# MicroBreeze.net
KiCad netlist of a schematic drawn in EAGLE
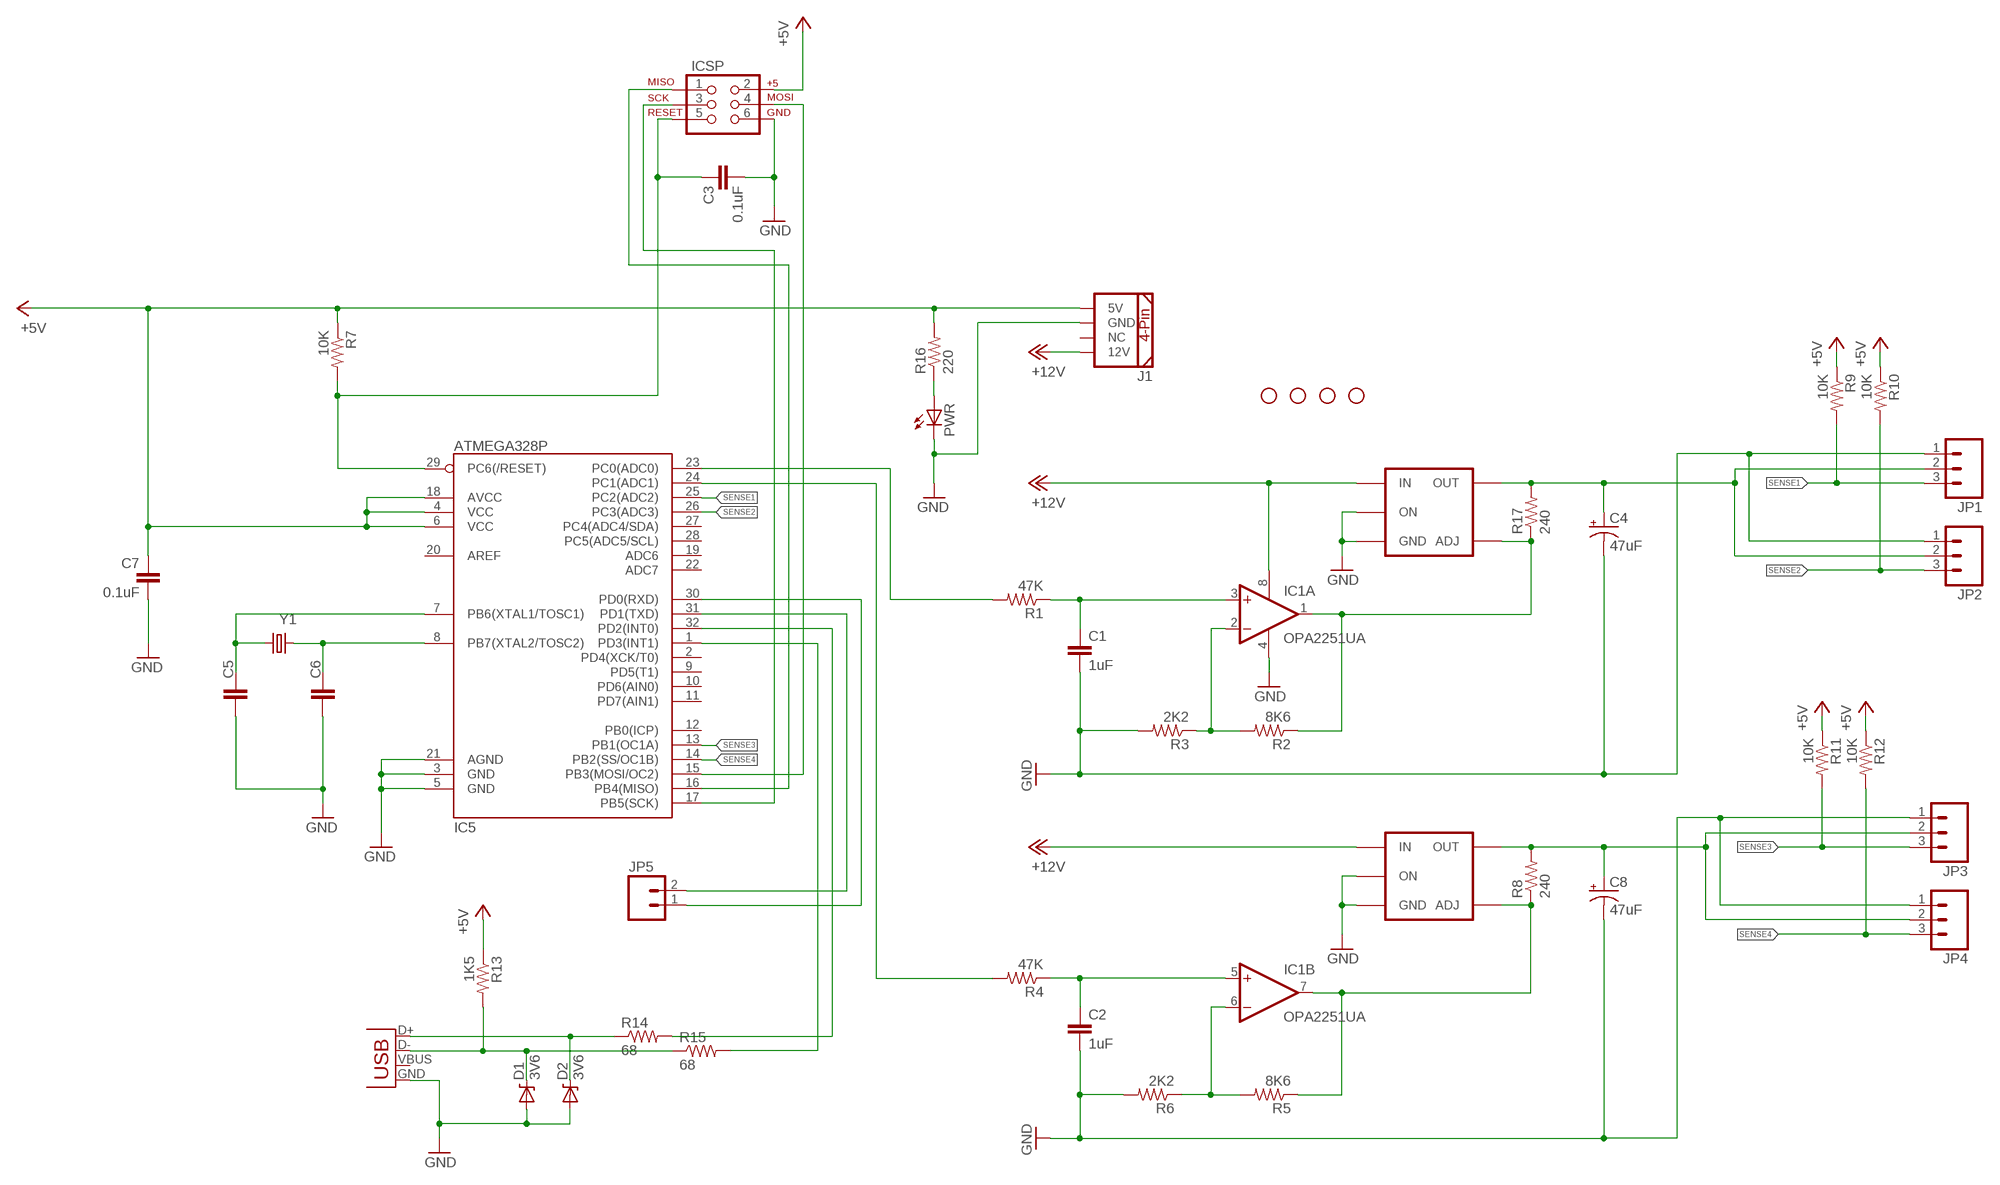
[diagram p0: schematic, sheet 1]

(export (version "E")
  (design (tool "Eeschema 10.0.6"))
  (components
    (comp (ref "C1")
      (value "1uF")
      (footprint "eagle-import:0805")
      (libsource (lib "eagle-import") (part "CAP0805"))
    )
    (comp (ref "C2")
      (value "1uF")
      (footprint "eagle-import:0805")
      (libsource (lib "eagle-import") (part "CAP0805"))
    )
    (comp (ref "C3")
      (value "0.1uF")
      (footprint "eagle-import:0805")
      (libsource (lib "eagle-import") (part "CAP0805"))
    )
    (comp (ref "C4")
      (value "47uF")
      (footprint "eagle-import:EIA3528")
      (libsource (lib "eagle-import") (part "47UF-TANT"))
    )
    (comp (ref "C5")
      (value ".22uF")
      (footprint "eagle-import:0805")
      (libsource (lib "eagle-import") (part "CAP0805"))
    )
    (comp (ref "C6")
      (value ".22uF")
      (footprint "eagle-import:0805")
      (libsource (lib "eagle-import") (part "CAP0805"))
    )
    (comp (ref "C7")
      (value "0.1uF")
      (footprint "eagle-import:0805")
      (libsource (lib "eagle-import") (part "CAP0805"))
    )
    (comp (ref "C8")
      (value "47uF")
      (footprint "eagle-import:EIA3528")
      (libsource (lib "eagle-import") (part "47UF-TANT"))
    )
    (comp (ref "D1")
      (value "3V6")
      (footprint "eagle-import:SOD-323")
      (libsource (lib "eagle-import") (part "DIODE-ZENER-BZT52"))
    )
    (comp (ref "D2")
      (value "3V6")
      (footprint "eagle-import:SOD-323")
      (libsource (lib "eagle-import") (part "DIODE-ZENER-BZT52"))
    )
    (comp (ref "HOLE1")
      (value "STAND-OFF")
      (footprint "eagle-import:STAND-OFF")
      (libsource (lib "eagle-import") (part "STAND-OFF"))
    )
    (comp (ref "HOLE2")
      (value "STAND-OFF")
      (footprint "eagle-import:STAND-OFF")
      (libsource (lib "eagle-import") (part "STAND-OFF"))
    )
    (comp (ref "HOLE3")
      (value "STAND-OFF")
      (footprint "eagle-import:STAND-OFF")
      (libsource (lib "eagle-import") (part "STAND-OFF"))
    )
    (comp (ref "HOLE4")
      (value "STAND-OFF")
      (footprint "eagle-import:STAND-OFF")
      (libsource (lib "eagle-import") (part "STAND-OFF"))
    )
    (comp (ref "IC1")
      (value "OPA2251UA")
      (footprint "eagle-import:SO08")
      (libsource (lib "eagle-import") (part "OPA2UA251"))
    )
    (comp (ref "IC3")
      (value "LM2941TO220-V")
      (footprint "eagle-import:TO220-51")
      (libsource (lib "eagle-import") (part "LM2941TO220-V"))
    )
    (comp (ref "IC4")
      (value "LM2941TO220-V")
      (footprint "eagle-import:TO220-51")
      (libsource (lib "eagle-import") (part "LM2941TO220-V"))
    )
    (comp (ref "IC5")
      (value "ATMEGA328P")
      (footprint "eagle-import:TQFP32-08")
      (libsource (lib "eagle-import") (part "ATMEGA328_SMT"))
    )
    (comp (ref "ICSP")
      (value "AVR_SPI_PRG_6PTH")
      (footprint "eagle-import:2X3")
      (libsource (lib "eagle-import") (part "AVR_SPI_PRG_6PTH"))
    )
    (comp (ref "J1")
      (value "COMPUTER-PERIPHERAL-POWERVERTICAL")
      (footprint "eagle-import:COMPUTER-PERIPHERAL-POWER")
      (libsource (lib "eagle-import") (part "COMPUTER-PERIPHERAL-POWERVERTICAL"))
    )
    (comp (ref "JP1")
      (value "M03POLAR")
      (footprint "eagle-import:MOLEX-1X3")
      (libsource (lib "eagle-import") (part "M03POLAR"))
    )
    (comp (ref "JP2")
      (value "M03POLAR")
      (footprint "eagle-import:MOLEX-1X3")
      (libsource (lib "eagle-import") (part "M03POLAR"))
    )
    (comp (ref "JP3")
      (value "M03POLAR")
      (footprint "eagle-import:MOLEX-1X3")
      (libsource (lib "eagle-import") (part "M03POLAR"))
    )
    (comp (ref "JP4")
      (value "M03POLAR")
      (footprint "eagle-import:MOLEX-1X3")
      (libsource (lib "eagle-import") (part "M03POLAR"))
    )
    (comp (ref "JP5")
      (value "M02PTH")
      (footprint "eagle-import:1X02")
      (libsource (lib "eagle-import") (part "M02PTH"))
    )
    (comp (ref "PWR")
      (value "LED1206")
      (footprint "eagle-import:LED-1206")
      (libsource (lib "eagle-import") (part "LED1206"))
    )
    (comp (ref "R1")
      (value "47K")
      (footprint "eagle-import:0805")
      (libsource (lib "eagle-import") (part "RESISTOR0805-RES"))
    )
    (comp (ref "R2")
      (value "8K6")
      (footprint "eagle-import:0805")
      (libsource (lib "eagle-import") (part "RESISTOR0805-RES"))
    )
    (comp (ref "R3")
      (value "2K2")
      (footprint "eagle-import:0805")
      (libsource (lib "eagle-import") (part "RESISTOR0805-RES"))
    )
    (comp (ref "R4")
      (value "47K")
      (footprint "eagle-import:0805")
      (libsource (lib "eagle-import") (part "RESISTOR0805-RES"))
    )
    (comp (ref "R5")
      (value "8K6")
      (footprint "eagle-import:0805")
      (libsource (lib "eagle-import") (part "RESISTOR0805-RES"))
    )
    (comp (ref "R6")
      (value "2K2")
      (footprint "eagle-import:0805")
      (libsource (lib "eagle-import") (part "RESISTOR0805-RES"))
    )
    (comp (ref "R7")
      (value "10K")
      (footprint "eagle-import:0805")
      (libsource (lib "eagle-import") (part "RESISTOR0805-RES"))
    )
    (comp (ref "R8")
      (value "240")
      (footprint "eagle-import:0805")
      (libsource (lib "eagle-import") (part "RESISTOR0805-RES"))
    )
    (comp (ref "R9")
      (value "10K")
      (footprint "eagle-import:0805")
      (libsource (lib "eagle-import") (part "RESISTOR0805-RES"))
    )
    (comp (ref "R10")
      (value "10K")
      (footprint "eagle-import:0805")
      (libsource (lib "eagle-import") (part "RESISTOR0805-RES"))
    )
    (comp (ref "R11")
      (value "10K")
      (footprint "eagle-import:0805")
      (libsource (lib "eagle-import") (part "RESISTOR0805-RES"))
    )
    (comp (ref "R12")
      (value "10K")
      (footprint "eagle-import:0805")
      (libsource (lib "eagle-import") (part "RESISTOR0805-RES"))
    )
    (comp (ref "R13")
      (value "1K5")
      (footprint "eagle-import:0805")
      (libsource (lib "eagle-import") (part "RESISTOR0805-RES"))
    )
    (comp (ref "R14")
      (value "68")
      (footprint "eagle-import:0805")
      (libsource (lib "eagle-import") (part "RESISTOR0805-RES"))
    )
    (comp (ref "R15")
      (value "68")
      (footprint "eagle-import:0805")
      (libsource (lib "eagle-import") (part "RESISTOR0805-RES"))
    )
    (comp (ref "R16")
      (value "220")
      (footprint "eagle-import:0805")
      (libsource (lib "eagle-import") (part "RESISTOR0805-RES"))
    )
    (comp (ref "R17")
      (value "240")
      (footprint "eagle-import:0805")
      (libsource (lib "eagle-import") (part "RESISTOR0805-RES"))
    )
    (comp (ref "USB")
      (value "USB-A-SMD")
      (footprint "eagle-import:USB-A-S-NOSILK-FEMALE")
      (libsource (lib "eagle-import") (part "USB-A-SMD"))
    )
    (comp (ref "Y1")
      (value "16MHZ")
      (footprint "eagle-import:HC49US")
      (libsource (lib "eagle-import") (part "CRYSTALHC49US"))
    )
  )
  (nets
    (net (code "1") (name "+5V") (class "Default")
      (node (ref "C7") (pin "1") (pinfunction "1_1") (pintype "passive"))
      (node (ref "IC5") (pin "18") (pinfunction "AVCC_18") (pintype "bidirectional"))
      (node (ref "IC5") (pin "4") (pinfunction "VCC_4") (pintype "bidirectional"))
      (node (ref "IC5") (pin "6") (pinfunction "VCC_6") (pintype "bidirectional"))
      (node (ref "ICSP") (pin "2") (pinfunction "2_2") (pintype "passive"))
      (node (ref "J1") (pin "5V") (pinfunction "5V_5V") (pintype "passive"))
      (node (ref "R10") (pin "1") (pinfunction "1_1") (pintype "passive"))
      (node (ref "R11") (pin "1") (pinfunction "1_1") (pintype "passive"))
      (node (ref "R12") (pin "1") (pinfunction "1_1") (pintype "passive"))
      (node (ref "R13") (pin "1") (pinfunction "1_1") (pintype "passive"))
      (node (ref "R16") (pin "2") (pinfunction "2_2") (pintype "passive"))
      (node (ref "R7") (pin "1") (pinfunction "1_1") (pintype "passive"))
      (node (ref "R9") (pin "1") (pinfunction "1_1") (pintype "passive"))
    )
    (net (code "2") (name "+12V") (class "Default")
      (node (ref "IC1") (pin "8") (pinfunction "V+_8") (pintype "power_in"))
      (node (ref "IC3") (pin "4") (pinfunction "IN_4") (pintype "bidirectional"))
      (node (ref "IC4") (pin "4") (pinfunction "IN_4") (pintype "bidirectional"))
      (node (ref "J1") (pin "12V") (pinfunction "12V_12V") (pintype "passive"))
    )
    (net (code "3") (name "GND") (class "Default")
      (node (ref "C1") (pin "2") (pinfunction "2_2") (pintype "passive"))
      (node (ref "C2") (pin "2") (pinfunction "2_2") (pintype "passive"))
      (node (ref "C3") (pin "2") (pinfunction "2_2") (pintype "passive"))
      (node (ref "C4") (pin "C") (pinfunction "-_C") (pintype "passive"))
      (node (ref "C5") (pin "2") (pinfunction "2_2") (pintype "passive"))
      (node (ref "C6") (pin "2") (pinfunction "2_2") (pintype "passive"))
      (node (ref "C7") (pin "2") (pinfunction "2_2") (pintype "passive"))
      (node (ref "C8") (pin "C") (pinfunction "-_C") (pintype "passive"))
      (node (ref "D1") (pin "2") (pinfunction "A_2") (pintype "passive"))
      (node (ref "D2") (pin "2") (pinfunction "A_2") (pintype "passive"))
      (node (ref "IC1") (pin "4") (pinfunction "V-_4") (pintype "power_in"))
      (node (ref "IC3") (pin "2") (pinfunction "ON_2") (pintype "bidirectional"))
      (node (ref "IC3") (pin "3") (pinfunction "GND_3") (pintype "bidirectional"))
      (node (ref "IC4") (pin "2") (pinfunction "ON_2") (pintype "bidirectional"))
      (node (ref "IC4") (pin "3") (pinfunction "GND_3") (pintype "bidirectional"))
      (node (ref "IC5") (pin "21") (pinfunction "AGND_21") (pintype "bidirectional"))
      (node (ref "IC5") (pin "3") (pinfunction "GND_3") (pintype "bidirectional"))
      (node (ref "IC5") (pin "5") (pinfunction "GND_5") (pintype "bidirectional"))
      (node (ref "ICSP") (pin "6") (pinfunction "6_6") (pintype "passive"))
      (node (ref "J1") (pin "GND") (pinfunction "GND_GND") (pintype "passive"))
      (node (ref "JP1") (pin "1") (pinfunction "1_1") (pintype "passive"))
      (node (ref "JP2") (pin "1") (pinfunction "1_1") (pintype "passive"))
      (node (ref "JP3") (pin "1") (pinfunction "1_1") (pintype "passive"))
      (node (ref "JP4") (pin "1") (pinfunction "1_1") (pintype "passive"))
      (node (ref "PWR") (pin "C") (pinfunction "C_C") (pintype "passive"))
      (node (ref "R3") (pin "2") (pinfunction "2_2") (pintype "passive"))
      (node (ref "R6") (pin "2") (pinfunction "2_2") (pintype "passive"))
      (node (ref "USB") (pin "GND") (pinfunction "GND_GND") (pintype "bidirectional"))
    )
    (net (code "4") (name "Net-(C4-+)") (class "Default")
      (node (ref "C4") (pin "A") (pinfunction "+_A") (pintype "passive"))
      (node (ref "IC3") (pin "5") (pinfunction "OUT_5") (pintype "bidirectional"))
      (node (ref "JP1") (pin "2") (pinfunction "2_2") (pintype "passive"))
      (node (ref "JP2") (pin "2") (pinfunction "2_2") (pintype "passive"))
      (node (ref "R17") (pin "2") (pinfunction "2_2") (pintype "passive"))
    )
    (net (code "5") (name "Net-(C8-+)") (class "Default")
      (node (ref "C8") (pin "A") (pinfunction "+_A") (pintype "passive"))
      (node (ref "IC4") (pin "5") (pinfunction "OUT_5") (pintype "bidirectional"))
      (node (ref "JP3") (pin "2") (pinfunction "2_2") (pintype "passive"))
      (node (ref "JP4") (pin "2") (pinfunction "2_2") (pintype "passive"))
      (node (ref "R8") (pin "2") (pinfunction "2_2") (pintype "passive"))
    )
    (net (code "6") (name "Net-(D1-C)") (class "Default")
      (node (ref "D1") (pin "1") (pinfunction "C_1") (pintype "passive"))
      (node (ref "R13") (pin "2") (pinfunction "2_2") (pintype "passive"))
      (node (ref "R15") (pin "1") (pinfunction "1_1") (pintype "passive"))
      (node (ref "USB") (pin "D-") (pinfunction "D-_D-") (pintype "bidirectional"))
    )
    (net (code "7") (name "Net-(D2-C)") (class "Default")
      (node (ref "D2") (pin "1") (pinfunction "C_1") (pintype "passive"))
      (node (ref "R14") (pin "1") (pinfunction "1_1") (pintype "passive"))
      (node (ref "USB") (pin "D+") (pinfunction "D+_D+") (pintype "bidirectional"))
    )
    (net (code "8") (name "Net-(IC1A-+IN)") (class "Default")
      (node (ref "C1") (pin "1") (pinfunction "1_1") (pintype "passive"))
      (node (ref "IC1") (pin "3") (pinfunction "+IN_3") (pintype "input"))
      (node (ref "R1") (pin "1") (pinfunction "1_1") (pintype "passive"))
    )
    (net (code "9") (name "Net-(IC1A--IN)") (class "Default")
      (node (ref "IC1") (pin "2") (pinfunction "-IN_2") (pintype "input"))
      (node (ref "R2") (pin "2") (pinfunction "2_2") (pintype "passive"))
      (node (ref "R3") (pin "1") (pinfunction "1_1") (pintype "passive"))
    )
    (net (code "10") (name "Net-(IC1A-OUT)") (class "Default")
      (node (ref "IC1") (pin "1") (pinfunction "OUT_1") (pintype "output"))
      (node (ref "IC3") (pin "1") (pinfunction "ADJ_1") (pintype "bidirectional"))
      (node (ref "R17") (pin "1") (pinfunction "1_1") (pintype "passive"))
      (node (ref "R2") (pin "1") (pinfunction "1_1") (pintype "passive"))
    )
    (net (code "11") (name "Net-(IC1B-+IN)") (class "Default")
      (node (ref "C2") (pin "1") (pinfunction "1_1") (pintype "passive"))
      (node (ref "IC1") (pin "5") (pinfunction "+IN_5") (pintype "input"))
      (node (ref "R4") (pin "1") (pinfunction "1_1") (pintype "passive"))
    )
    (net (code "12") (name "Net-(IC1B--IN)") (class "Default")
      (node (ref "IC1") (pin "6") (pinfunction "-IN_6") (pintype "input"))
      (node (ref "R5") (pin "2") (pinfunction "2_2") (pintype "passive"))
      (node (ref "R6") (pin "1") (pinfunction "1_1") (pintype "passive"))
    )
    (net (code "13") (name "Net-(IC1B-OUT)") (class "Default")
      (node (ref "IC1") (pin "7") (pinfunction "OUT_7") (pintype "output"))
      (node (ref "IC4") (pin "1") (pinfunction "ADJ_1") (pintype "bidirectional"))
      (node (ref "R5") (pin "1") (pinfunction "1_1") (pintype "passive"))
      (node (ref "R8") (pin "1") (pinfunction "1_1") (pintype "passive"))
    )
    (net (code "14") (name "Net-(IC5-PB3(MOSI{slash}OC2))") (class "Default")
      (node (ref "IC5") (pin "15") (pinfunction "PB3(MOSI/OC2)_15") (pintype "bidirectional"))
      (node (ref "ICSP") (pin "4") (pinfunction "4_4") (pintype "passive"))
    )
    (net (code "15") (name "Net-(IC5-PB4(MISO))") (class "Default")
      (node (ref "IC5") (pin "16") (pinfunction "PB4(MISO)_16") (pintype "bidirectional"))
      (node (ref "ICSP") (pin "1") (pinfunction "1_1") (pintype "passive"))
    )
    (net (code "16") (name "Net-(IC5-PB5(SCK))") (class "Default")
      (node (ref "IC5") (pin "17") (pinfunction "PB5(SCK)_17") (pintype "bidirectional"))
      (node (ref "ICSP") (pin "3") (pinfunction "3_3") (pintype "passive"))
    )
    (net (code "17") (name "Net-(IC5-PB6(XTAL1{slash}TOSC1))") (class "Default")
      (node (ref "C5") (pin "1") (pinfunction "1_1") (pintype "passive"))
      (node (ref "IC5") (pin "7") (pinfunction "PB6(XTAL1/TOSC1)_7") (pintype "bidirectional"))
      (node (ref "Y1") (pin "2") (pinfunction "2_2") (pintype "passive"))
    )
    (net (code "18") (name "Net-(IC5-PB7(XTAL2{slash}TOSC2))") (class "Default")
      (node (ref "C6") (pin "1") (pinfunction "1_1") (pintype "passive"))
      (node (ref "IC5") (pin "8") (pinfunction "PB7(XTAL2/TOSC2)_8") (pintype "bidirectional"))
      (node (ref "Y1") (pin "1") (pinfunction "1_1") (pintype "passive"))
    )
    (net (code "19") (name "Net-(IC5-PC0(ADC0))") (class "Default")
      (node (ref "IC5") (pin "23") (pinfunction "PC0(ADC0)_23") (pintype "bidirectional"))
      (node (ref "R1") (pin "2") (pinfunction "2_2") (pintype "passive"))
    )
    (net (code "20") (name "Net-(IC5-PC1(ADC1))") (class "Default")
      (node (ref "IC5") (pin "24") (pinfunction "PC1(ADC1)_24") (pintype "bidirectional"))
      (node (ref "R4") (pin "2") (pinfunction "2_2") (pintype "passive"))
    )
    (net (code "21") (name "Net-(IC5-PC6({slash}RESET))") (class "Default")
      (node (ref "C3") (pin "1") (pinfunction "1_1") (pintype "passive"))
      (node (ref "IC5") (pin "29") (pinfunction "PC6(/RESET)_29") (pintype "bidirectional"))
      (node (ref "ICSP") (pin "5") (pinfunction "5_5") (pintype "passive"))
      (node (ref "R7") (pin "2") (pinfunction "2_2") (pintype "passive"))
    )
    (net (code "22") (name "Net-(IC5-PD0(RXD))") (class "Default")
      (node (ref "IC5") (pin "30") (pinfunction "PD0(RXD)_30") (pintype "bidirectional"))
      (node (ref "JP5") (pin "1") (pinfunction "1_1") (pintype "passive"))
    )
    (net (code "23") (name "Net-(IC5-PD1(TXD))") (class "Default")
      (node (ref "IC5") (pin "31") (pinfunction "PD1(TXD)_31") (pintype "bidirectional"))
      (node (ref "JP5") (pin "2") (pinfunction "2_2") (pintype "passive"))
    )
    (net (code "24") (name "Net-(IC5-PD2(INT0))") (class "Default")
      (node (ref "IC5") (pin "32") (pinfunction "PD2(INT0)_32") (pintype "bidirectional"))
      (node (ref "R14") (pin "2") (pinfunction "2_2") (pintype "passive"))
    )
    (net (code "25") (name "Net-(IC5-PD3(INT1))") (class "Default")
      (node (ref "IC5") (pin "1") (pinfunction "PD3(INT1)_1") (pintype "bidirectional"))
      (node (ref "R15") (pin "2") (pinfunction "2_2") (pintype "passive"))
    )
    (net (code "26") (name "Net-(PWR-PadA)") (class "Default")
      (node (ref "PWR") (pin "A") (pinfunction "A_A") (pintype "passive"))
      (node (ref "R16") (pin "1") (pinfunction "1_1") (pintype "passive"))
    )
    (net (code "27") (name "SENSE1") (class "Default")
      (node (ref "IC5") (pin "25") (pinfunction "PC2(ADC2)_25") (pintype "bidirectional"))
      (node (ref "JP1") (pin "3") (pinfunction "3_3") (pintype "passive"))
      (node (ref "R9") (pin "2") (pinfunction "2_2") (pintype "passive"))
    )
    (net (code "28") (name "SENSE2") (class "Default")
      (node (ref "IC5") (pin "26") (pinfunction "PC3(ADC3)_26") (pintype "bidirectional"))
      (node (ref "JP2") (pin "3") (pinfunction "3_3") (pintype "passive"))
      (node (ref "R10") (pin "2") (pinfunction "2_2") (pintype "passive"))
    )
    (net (code "29") (name "SENSE3") (class "Default")
      (node (ref "IC5") (pin "13") (pinfunction "PB1(OC1A)_13") (pintype "bidirectional"))
      (node (ref "JP3") (pin "3") (pinfunction "3_3") (pintype "passive"))
      (node (ref "R11") (pin "2") (pinfunction "2_2") (pintype "passive"))
    )
    (net (code "30") (name "SENSE4") (class "Default")
      (node (ref "IC5") (pin "14") (pinfunction "PB2(SS/OC1B)_14") (pintype "bidirectional"))
      (node (ref "JP4") (pin "3") (pinfunction "3_3") (pintype "passive"))
      (node (ref "R12") (pin "2") (pinfunction "2_2") (pintype "passive"))
    )
    (net (code "31") (name "unconnected-(IC5-ADC6-Pad19)") (class "Default")
      (node (ref "IC5") (pin "19") (pinfunction "ADC6_19") (pintype "bidirectional"))
    )
    (net (code "32") (name "unconnected-(IC5-ADC7-Pad22)") (class "Default")
      (node (ref "IC5") (pin "22") (pinfunction "ADC7_22") (pintype "bidirectional"))
    )
    (net (code "33") (name "unconnected-(IC5-AREF-Pad20)") (class "Default")
      (node (ref "IC5") (pin "20") (pinfunction "AREF_20") (pintype "bidirectional"))
    )
    (net (code "34") (name "unconnected-(IC5-PB0(ICP)-Pad12)") (class "Default")
      (node (ref "IC5") (pin "12") (pinfunction "PB0(ICP)_12") (pintype "bidirectional"))
    )
    (net (code "35") (name "unconnected-(IC5-PC4(ADC4{slash}SDA)-Pad27)") (class "Default")
      (node (ref "IC5") (pin "27") (pinfunction "PC4(ADC4/SDA)_27") (pintype "bidirectional"))
    )
    (net (code "36") (name "unconnected-(IC5-PC5(ADC5{slash}SCL)-Pad28)") (class "Default")
      (node (ref "IC5") (pin "28") (pinfunction "PC5(ADC5/SCL)_28") (pintype "bidirectional"))
    )
    (net (code "37") (name "unconnected-(IC5-PD4(XCK{slash}T0)-Pad2)") (class "Default")
      (node (ref "IC5") (pin "2") (pinfunction "PD4(XCK/T0)_2") (pintype "bidirectional"))
    )
    (net (code "38") (name "unconnected-(IC5-PD5(T1)-Pad9)") (class "Default")
      (node (ref "IC5") (pin "9") (pinfunction "PD5(T1)_9") (pintype "bidirectional"))
    )
    (net (code "39") (name "unconnected-(IC5-PD6(AIN0)-Pad10)") (class "Default")
      (node (ref "IC5") (pin "10") (pinfunction "PD6(AIN0)_10") (pintype "bidirectional"))
    )
    (net (code "40") (name "unconnected-(IC5-PD7(AIN1)-Pad11)") (class "Default")
      (node (ref "IC5") (pin "11") (pinfunction "PD7(AIN1)_11") (pintype "bidirectional"))
    )
    (net (code "41") (name "unconnected-(J1-PadNC)") (class "Default")
      (node (ref "J1") (pin "NC") (pinfunction "NC_NC") (pintype "passive"))
    )
    (net (code "42") (name "unconnected-(USB-PadVBUS)") (class "Default")
      (node (ref "USB") (pin "VBUS") (pinfunction "VBUS_VBUS") (pintype "bidirectional"))
    )
  )
)
